# Main.net
KiCad netlist of a schematic drawn in Altium Designer
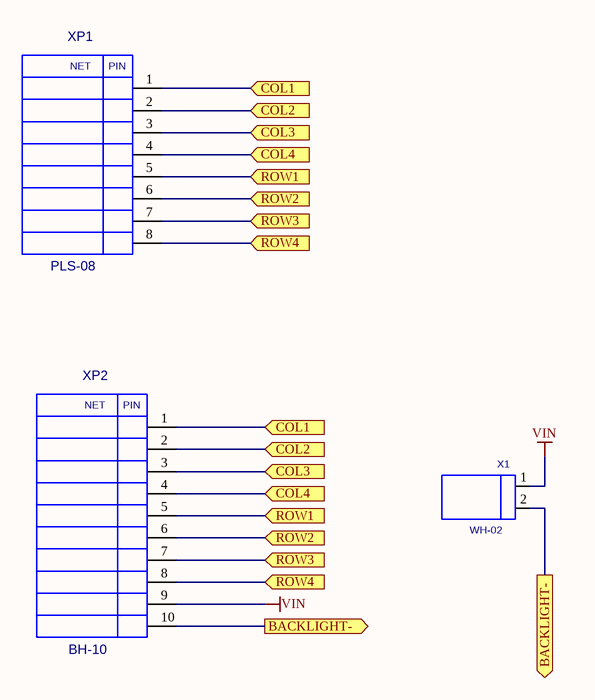
[diagram p0: Main.SchDoc]

(export (version "E")
  (design (tool "Eeschema 10.0.6"))
  (components
    (comp (ref "X1") (value "WH-02") (footprint "WH-02") (libsource (lib "fizik_lib") (part "WH-02")))
    (comp (ref "XP1") (value "PLS-08") (footprint "PLS-08") (libsource (lib "fizik_lib") (part "PLS-08")))
    (comp (ref "XP2") (value "BH-10") (footprint "BH-10") (libsource (lib "fizik_lib") (part "BH-10")))
  )
  (nets
    (net (code "1") (name "/BACKLIGHT-") (class "Default")
      (node (ref "X1") (pin "2") (pinfunction "2_2") (pintype "passive"))
      (node (ref "XP2") (pin "10") (pinfunction "10_10") (pintype "passive"))
    )
    (net (code "2") (name "/COL1") (class "Default")
      (node (ref "XP1") (pin "1") (pinfunction "1_1") (pintype "passive"))
      (node (ref "XP2") (pin "1") (pinfunction "1_1") (pintype "passive"))
    )
    (net (code "3") (name "/COL2") (class "Default")
      (node (ref "XP1") (pin "2") (pinfunction "2_2") (pintype "passive"))
      (node (ref "XP2") (pin "2") (pinfunction "2_2") (pintype "passive"))
    )
    (net (code "4") (name "/COL3") (class "Default")
      (node (ref "XP1") (pin "3") (pinfunction "3_3") (pintype "passive"))
      (node (ref "XP2") (pin "3") (pinfunction "3_3") (pintype "passive"))
    )
    (net (code "5") (name "/COL4") (class "Default")
      (node (ref "XP1") (pin "4") (pinfunction "4_4") (pintype "passive"))
      (node (ref "XP2") (pin "4") (pinfunction "4_4") (pintype "passive"))
    )
    (net (code "6") (name "/ROW1") (class "Default")
      (node (ref "XP1") (pin "5") (pinfunction "5_5") (pintype "passive"))
      (node (ref "XP2") (pin "5") (pinfunction "5_5") (pintype "passive"))
    )
    (net (code "7") (name "/ROW2") (class "Default")
      (node (ref "XP1") (pin "6") (pinfunction "6_6") (pintype "passive"))
      (node (ref "XP2") (pin "6") (pinfunction "6_6") (pintype "passive"))
    )
    (net (code "8") (name "/ROW3") (class "Default")
      (node (ref "XP1") (pin "7") (pinfunction "7_7") (pintype "passive"))
      (node (ref "XP2") (pin "7") (pinfunction "7_7") (pintype "passive"))
    )
    (net (code "9") (name "/ROW4") (class "Default")
      (node (ref "XP1") (pin "8") (pinfunction "8_8") (pintype "passive"))
      (node (ref "XP2") (pin "8") (pinfunction "8_8") (pintype "passive"))
    )
    (net (code "10") (name "VIN") (class "Default")
      (node (ref "X1") (pin "1") (pinfunction "1_1") (pintype "passive"))
      (node (ref "XP2") (pin "9") (pinfunction "9_9") (pintype "passive"))
    )
  )
)
